# StepperMotorDriver_Ver_0_1.net
KiCad netlist of a schematic drawn in Altium Designer
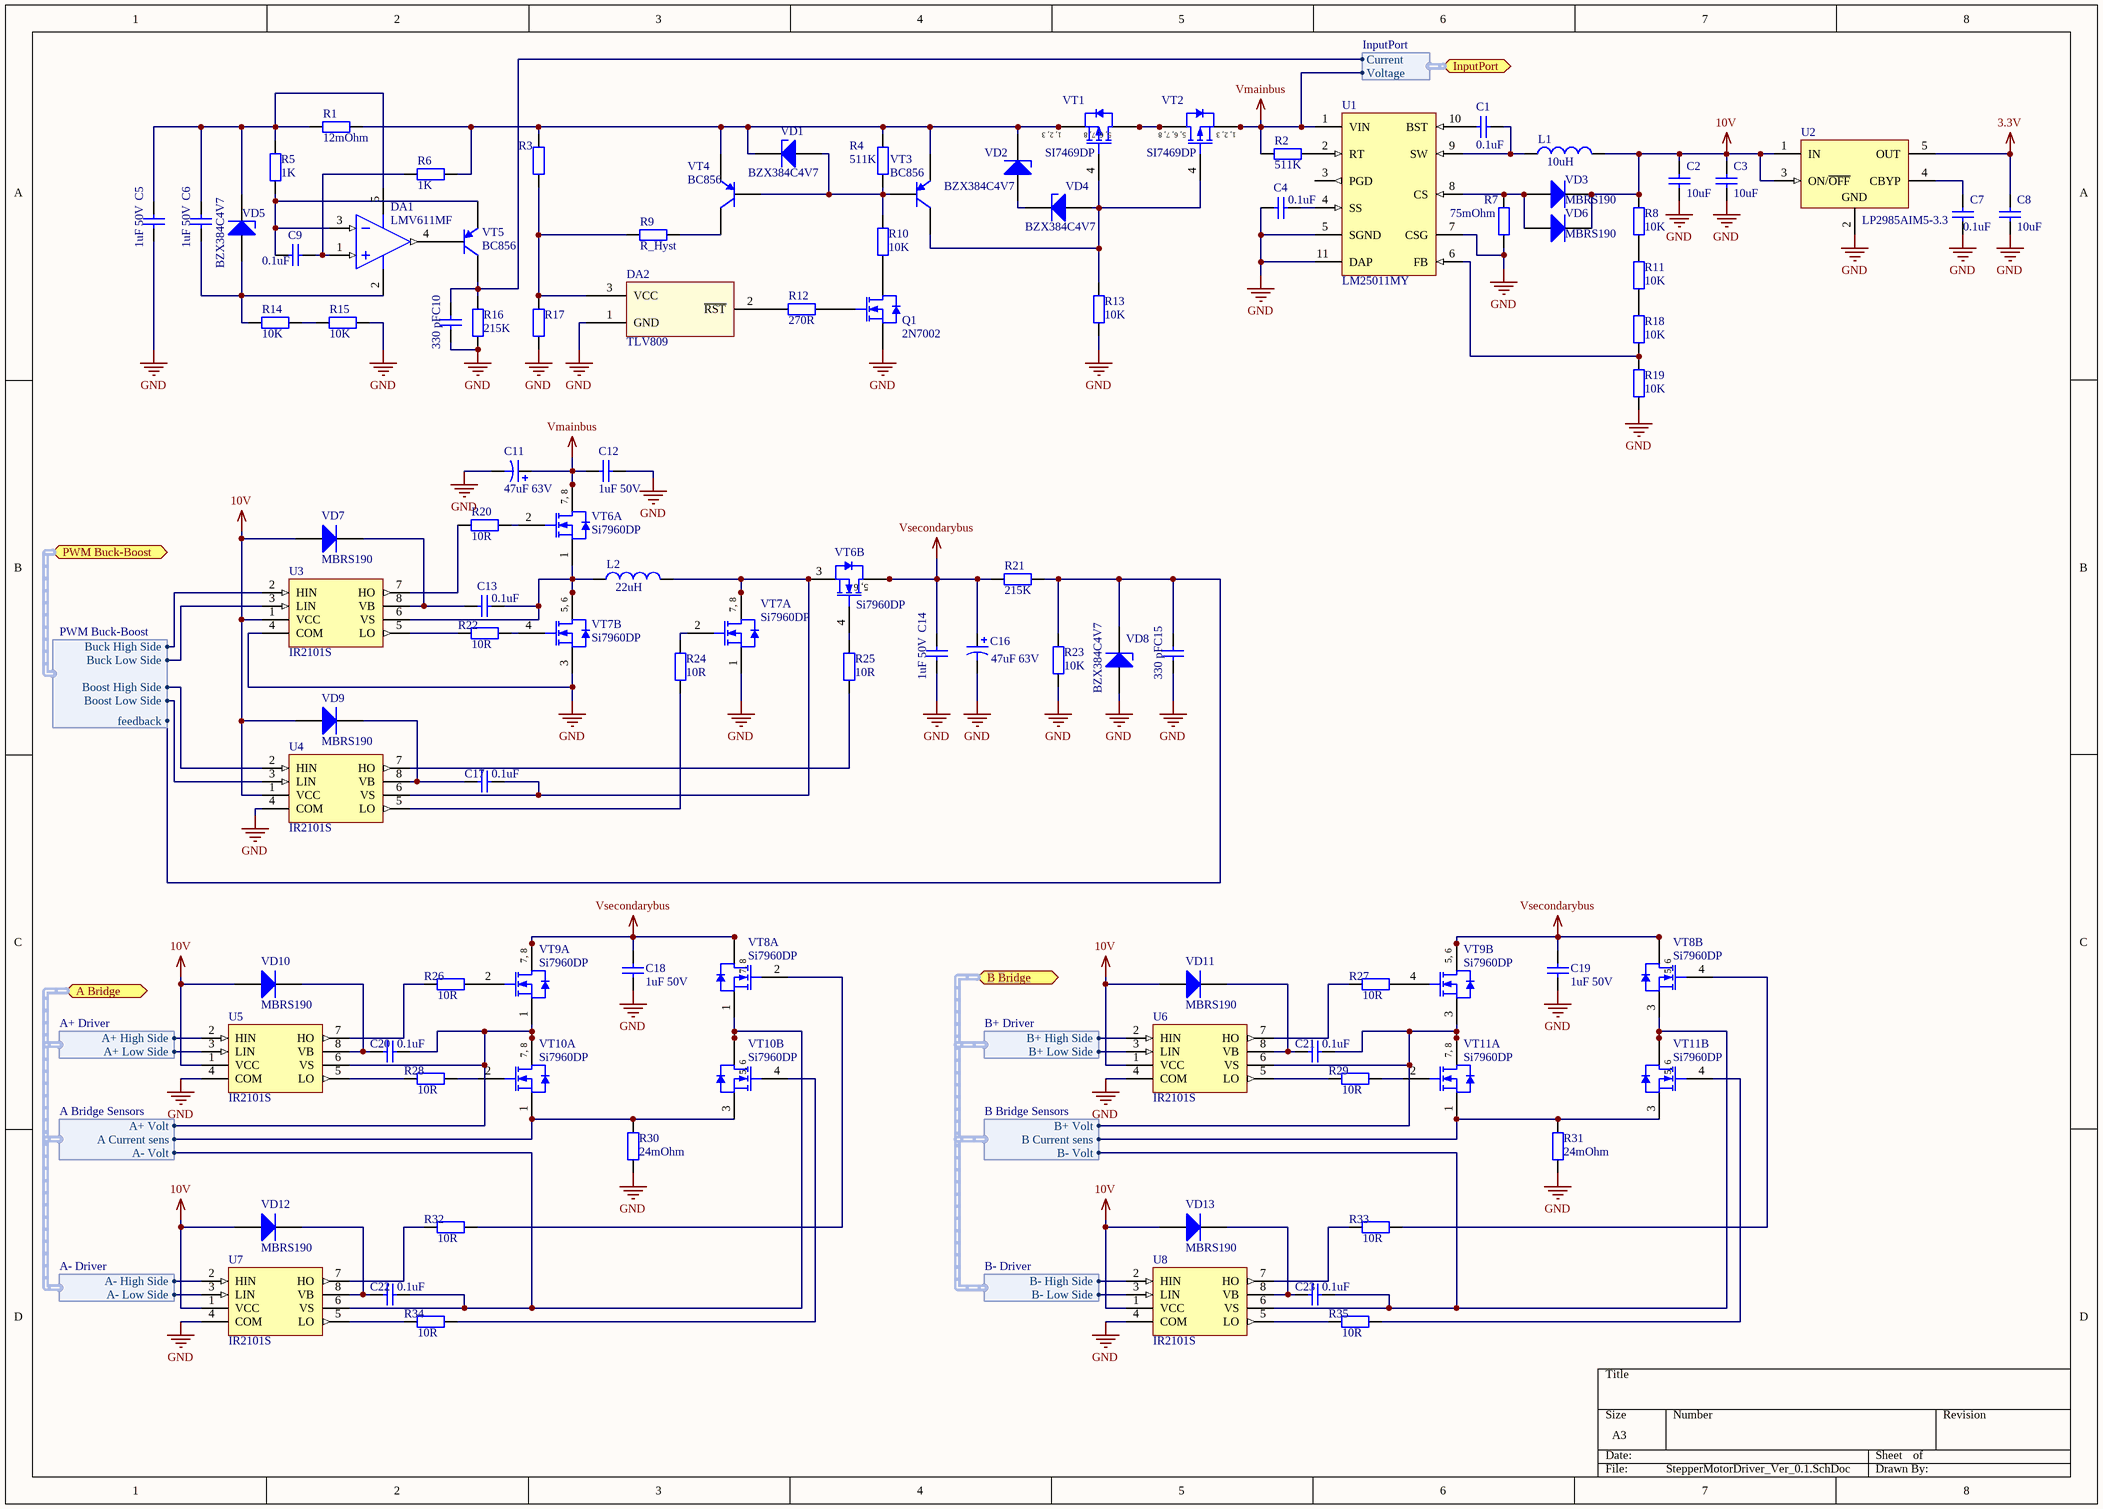
[diagram p0: StepperMotorDriver_Ver_0.1.SchDoc]

(export (version "E")
  (design (tool "Eeschema 10.0.6"))
  (components
    (comp (ref "C1")
      (value "0.1uF")
      (footprint "1608[0603]")
      (description "Capacitor")
      (fields (field (name "PUBLISHER") "Altium Limited"))
      (libsource (lib "SMD") (part "Capacitor"))
    )
    (comp (ref "C2")
      (value "10uF")
      (footprint "C1206")
      (description "Capacitor")
      (fields (field (name "PUBLISHER") "Altium Limited"))
      (libsource (lib "SMD") (part "Capacitor"))
    )
    (comp (ref "C3")
      (value "10uF")
      (footprint "C1206")
      (description "Capacitor")
      (fields (field (name "PUBLISHER") "Altium Limited"))
      (libsource (lib "SMD") (part "Capacitor"))
    )
    (comp (ref "C4")
      (value "0.1uF")
      (footprint "1608[0603]")
      (description "Capacitor")
      (fields (field (name "PUBLISHER") "Altium Limited"))
      (libsource (lib "SMD") (part "Capacitor"))
    )
    (comp (ref "C5")
      (value "1uF 50V")
      (footprint "C0805")
      (description "Capacitor")
      (fields (field (name "PUBLISHER") "Altium Limited"))
      (libsource (lib "SMD") (part "Capacitor"))
    )
    (comp (ref "C6")
      (value "1uF 50V")
      (footprint "C0805")
      (description "Capacitor")
      (fields (field (name "PUBLISHER") "Altium Limited"))
      (libsource (lib "SMD") (part "Capacitor"))
    )
    (comp (ref "C7")
      (value "0.1uF")
      (footprint "1608[0603]")
      (description "Capacitor")
      (fields (field (name "PUBLISHER") "Altium Limited"))
      (libsource (lib "SMD") (part "Capacitor"))
    )
    (comp (ref "C8")
      (value "10uF")
      (footprint "C1206")
      (description "Capacitor")
      (fields (field (name "PUBLISHER") "Altium Limited"))
      (libsource (lib "SMD") (part "Capacitor"))
    )
    (comp (ref "C9")
      (value "0.1uF")
      (footprint "1608[0603]")
      (description "Capacitor")
      (fields (field (name "PUBLISHER") "Altium Limited"))
      (libsource (lib "SMD") (part "Capacitor"))
    )
    (comp (ref "C10")
      (value "330 pF")
      (footprint "1608[0603]")
      (description "Capacitor")
      (fields (field (name "PUBLISHER") "Altium Limited"))
      (libsource (lib "SMD") (part "Capacitor"))
    )
    (comp (ref "C11")
      (value "47uF 63V")
      (footprint "SMD:10x10.5")
      (description "Polarized Capacitor (Radial)")
      (fields (field (name "PUBLISHER") "Altium Limited"))
      (libsource (lib "Miscellaneous Devices") (part "Cap Pol1"))
    )
    (comp (ref "C12")
      (value "1uF 50V")
      (footprint "C0805")
      (description "Capacitor")
      (fields (field (name "PUBLISHER") "Altium Limited"))
      (libsource (lib "SMD") (part "Capacitor"))
    )
    (comp (ref "C13")
      (value "0.1uF")
      (footprint "1608[0603]")
      (description "Capacitor")
      (fields (field (name "PUBLISHER") "Altium Limited"))
      (libsource (lib "SMD") (part "Capacitor"))
    )
    (comp (ref "C14")
      (value "1uF 50V")
      (footprint "C0805")
      (description "Capacitor")
      (fields (field (name "PUBLISHER") "Altium Limited"))
      (libsource (lib "SMD") (part "Capacitor"))
    )
    (comp (ref "C15")
      (value "330 pF")
      (footprint "1608[0603]")
      (description "Capacitor")
      (fields (field (name "PUBLISHER") "Altium Limited"))
      (libsource (lib "SMD") (part "Capacitor"))
    )
    (comp (ref "C16")
      (value "47uF 63V")
      (footprint "10x10.5")
      (description "Polarized Capacitor (Radial)")
      (fields (field (name "PUBLISHER") "Altium Limited"))
      (libsource (lib "Miscellaneous Devices") (part "Cap Pol1"))
    )
    (comp (ref "C17")
      (value "0.1uF")
      (footprint "1608[0603]")
      (description "Capacitor")
      (fields (field (name "PUBLISHER") "Altium Limited"))
      (libsource (lib "SMD") (part "Capacitor"))
    )
    (comp (ref "C18")
      (value "1uF 50V")
      (footprint "C0805")
      (description "Capacitor")
      (fields (field (name "PUBLISHER") "Altium Limited"))
      (libsource (lib "SMD") (part "Capacitor"))
    )
    (comp (ref "C19")
      (value "1uF 50V")
      (footprint "C0805")
      (description "Capacitor")
      (fields (field (name "PUBLISHER") "Altium Limited"))
      (libsource (lib "SMD") (part "Capacitor"))
    )
    (comp (ref "C20")
      (value "0.1uF")
      (footprint "1608[0603]")
      (description "Capacitor")
      (fields (field (name "PUBLISHER") "Altium Limited"))
      (libsource (lib "SMD") (part "Capacitor"))
    )
    (comp (ref "C21")
      (value "0.1uF")
      (footprint "1608[0603]")
      (description "Capacitor")
      (fields (field (name "PUBLISHER") "Altium Limited"))
      (libsource (lib "SMD") (part "Capacitor"))
    )
    (comp (ref "C22")
      (value "0.1uF")
      (footprint "1608[0603]")
      (description "Capacitor")
      (fields (field (name "PUBLISHER") "Altium Limited"))
      (libsource (lib "SMD") (part "Capacitor"))
    )
    (comp (ref "C23")
      (value "0.1uF")
      (footprint "1608[0603]")
      (description "Capacitor")
      (fields (field (name "PUBLISHER") "Altium Limited"))
      (libsource (lib "SMD") (part "Capacitor"))
    )
    (comp (ref "DA1")
      (value "LMV611MF")
      (footprint "MF05A_M")
      (description "Low Power Single Op Amp, 5-pin SOT-23")
      (fields
        (field (name "PARTNUMBER") "LM321MF")
        (field (name "MANUFACTURER") "National Semiconductor")
        (field (name "PUBLISHER") "Altium Limited")
      )
      (libsource (lib "SMD") (part "LMV611MF"))
    )
    (comp (ref "DA2")
      (value "TLV809")
      (footprint "SOT23")
      (description "SuperVisor TI")
      (libsource (lib "SMD") (part "TLV809"))
    )
    (comp (ref "L1")
      (value "10uH")
      (footprint "0402-A")
      (description "Inductor")
      (fields (field (name "PUBLISHER") "Altium Limited"))
      (libsource (lib "SMD") (part "Inductor"))
    )
    (comp (ref "L2")
      (value "22uH")
      (footprint "0402-A")
      (description "Inductor")
      (fields (field (name "PUBLISHER") "Altium Limited"))
      (libsource (lib "SMD") (part "Inductor"))
    )
    (comp (ref "Q1")
      (value "2N7002")
      (footprint "SOT23_N")
      (description "N-channel Enhancement Mode Field-effect Transistor")
      (fields (field (name "PUBLISHER") "Altium Limited"))
      (libsource (lib "Philips Discrete MOSFET - Low Power") (part "2N7002"))
    )
    (comp (ref "R1")
      (value "12mOhm")
      (footprint "Res12mOhm")
      (description "Resistor")
      (fields (field (name "PUBLISHER") "Altium Limited"))
      (libsource (lib "SMD") (part "Resistor"))
    )
    (comp (ref "R2")
      (value "511K")
      (footprint "J1-0603")
      (description "Resistor")
      (fields (field (name "PUBLISHER") "Altium Limited"))
      (libsource (lib "SMD") (part "Resistor"))
    )
    (comp (ref "R3")
      (value "Resistor")
      (footprint "J1-0603")
      (fields (field (name "PUBLISHER") "Altium Limited"))
      (libsource (lib "") (part "Resistor_3"))
    )
    (comp (ref "R4")
      (value "511K")
      (footprint "J1-0603")
      (description "Resistor")
      (fields (field (name "PUBLISHER") "Altium Limited"))
      (libsource (lib "") (part "Resistor_3"))
    )
    (comp (ref "R5")
      (value "1K")
      (footprint "J1-0603")
      (description "Resistor")
      (fields (field (name "PUBLISHER") "Altium Limited"))
      (libsource (lib "") (part "Resistor_1"))
    )
    (comp (ref "R6")
      (value "1K")
      (footprint "J1-0603")
      (description "Resistor")
      (fields (field (name "PUBLISHER") "Altium Limited"))
      (libsource (lib "") (part "Resistor_2"))
    )
    (comp (ref "R7")
      (value "75mOhm")
      (footprint "J1-0603")
      (description "Resistor")
      (fields (field (name "PUBLISHER") "Altium Limited"))
      (libsource (lib "") (part "Resistor_1"))
    )
    (comp (ref "R8")
      (value "10K")
      (footprint "J1-0603")
      (description "Resistor")
      (fields (field (name "PUBLISHER") "Altium Limited"))
      (libsource (lib "") (part "Resistor_1"))
    )
    (comp (ref "R9")
      (value "R_Hyst")
      (footprint "J1-0603")
      (description "Resistor")
      (fields (field (name "PUBLISHER") "Altium Limited"))
      (libsource (lib "SMD") (part "Resistor"))
    )
    (comp (ref "R10")
      (value "10K")
      (footprint "J1-0603")
      (description "Resistor")
      (fields (field (name "PUBLISHER") "Altium Limited"))
      (libsource (lib "") (part "Resistor_3"))
    )
    (comp (ref "R11")
      (value "10K")
      (footprint "J1-0603")
      (description "Resistor")
      (fields (field (name "PUBLISHER") "Altium Limited"))
      (libsource (lib "") (part "Resistor_3"))
    )
    (comp (ref "R12")
      (value "270R")
      (footprint "J1-0603")
      (description "Resistor")
      (fields (field (name "PUBLISHER") "Altium Limited"))
      (libsource (lib "SMD") (part "Resistor"))
    )
    (comp (ref "R13")
      (value "10K")
      (footprint "J1-0603")
      (description "Resistor")
      (fields (field (name "PUBLISHER") "Altium Limited"))
      (libsource (lib "") (part "Resistor_1"))
    )
    (comp (ref "R14")
      (value "10K")
      (footprint "J1-0603")
      (description "Resistor")
      (fields (field (name "PUBLISHER") "Altium Limited"))
      (libsource (lib "SMD") (part "Resistor"))
    )
    (comp (ref "R15")
      (value "10K")
      (footprint "J1-0603")
      (description "Resistor")
      (fields (field (name "PUBLISHER") "Altium Limited"))
      (libsource (lib "SMD") (part "Resistor"))
    )
    (comp (ref "R16")
      (value "215K")
      (footprint "J1-0603")
      (description "Resistor")
      (fields (field (name "PUBLISHER") "Altium Limited"))
      (libsource (lib "") (part "Resistor_1"))
    )
    (comp (ref "R17")
      (value "Resistor")
      (footprint "J1-0603")
      (fields (field (name "PUBLISHER") "Altium Limited"))
      (libsource (lib "") (part "Resistor_3"))
    )
    (comp (ref "R18")
      (value "10K")
      (footprint "J1-0603")
      (description "Resistor")
      (fields (field (name "PUBLISHER") "Altium Limited"))
      (libsource (lib "") (part "Resistor_1"))
    )
    (comp (ref "R19")
      (value "10K")
      (footprint "J1-0603")
      (description "Resistor")
      (fields (field (name "PUBLISHER") "Altium Limited"))
      (libsource (lib "") (part "Resistor_1"))
    )
    (comp (ref "R20")
      (value "10R")
      (footprint "J1-0603")
      (description "Resistor")
      (fields (field (name "PUBLISHER") "Altium Limited"))
      (libsource (lib "SMD") (part "Resistor"))
    )
    (comp (ref "R21")
      (value "215K")
      (footprint "J1-0603")
      (description "Resistor")
      (fields (field (name "PUBLISHER") "Altium Limited"))
      (libsource (lib "") (part "Resistor_2"))
    )
    (comp (ref "R22")
      (value "10R")
      (footprint "J1-0603")
      (description "Resistor")
      (fields (field (name "PUBLISHER") "Altium Limited"))
      (libsource (lib "SMD") (part "Resistor"))
    )
    (comp (ref "R23")
      (value "10K")
      (footprint "J1-0603")
      (description "Resistor")
      (fields (field (name "PUBLISHER") "Altium Limited"))
      (libsource (lib "") (part "Resistor_1"))
    )
    (comp (ref "R24")
      (value "10R")
      (footprint "J1-0603")
      (description "Resistor")
      (fields (field (name "PUBLISHER") "Altium Limited"))
      (libsource (lib "") (part "Resistor_1"))
    )
    (comp (ref "R25")
      (value "10R")
      (footprint "J1-0603")
      (description "Resistor")
      (fields (field (name "PUBLISHER") "Altium Limited"))
      (libsource (lib "") (part "Resistor_1"))
    )
    (comp (ref "R26")
      (value "10R")
      (footprint "J1-0603")
      (description "Resistor")
      (fields (field (name "PUBLISHER") "Altium Limited"))
      (libsource (lib "SMD") (part "Resistor"))
    )
    (comp (ref "R27")
      (value "10R")
      (footprint "J1-0603")
      (description "Resistor")
      (fields (field (name "PUBLISHER") "Altium Limited"))
      (libsource (lib "SMD") (part "Resistor"))
    )
    (comp (ref "R28")
      (value "10R")
      (footprint "J1-0603")
      (description "Resistor")
      (fields (field (name "PUBLISHER") "Altium Limited"))
      (libsource (lib "SMD") (part "Resistor"))
    )
    (comp (ref "R29")
      (value "10R")
      (footprint "J1-0603")
      (description "Resistor")
      (fields (field (name "PUBLISHER") "Altium Limited"))
      (libsource (lib "SMD") (part "Resistor"))
    )
    (comp (ref "R30")
      (value "24mOhm")
      (footprint "Res24mOhm")
      (description "Resistor")
      (fields (field (name "PUBLISHER") "Altium Limited"))
      (libsource (lib "") (part "Resistor_1"))
    )
    (comp (ref "R31")
      (value "24mOhm")
      (footprint "Res24mOhm")
      (description "Resistor")
      (fields (field (name "PUBLISHER") "Altium Limited"))
      (libsource (lib "") (part "Resistor_1"))
    )
    (comp (ref "R32")
      (value "10R")
      (footprint "J1-0603")
      (description "Resistor")
      (fields (field (name "PUBLISHER") "Altium Limited"))
      (libsource (lib "SMD") (part "Resistor"))
    )
    (comp (ref "R33")
      (value "10R")
      (footprint "J1-0603")
      (description "Resistor")
      (fields (field (name "PUBLISHER") "Altium Limited"))
      (libsource (lib "SMD") (part "Resistor"))
    )
    (comp (ref "R34")
      (value "10R")
      (footprint "J1-0603")
      (description "Resistor")
      (fields (field (name "PUBLISHER") "Altium Limited"))
      (libsource (lib "SMD") (part "Resistor"))
    )
    (comp (ref "R35")
      (value "10R")
      (footprint "J1-0603")
      (description "Resistor")
      (fields (field (name "PUBLISHER") "Altium Limited"))
      (libsource (lib "SMD") (part "Resistor"))
    )
    (comp (ref "U1")
      (value "LM25011MY")
      (footprint "MUC10A_N")
      (description "42V, 2A Constant On-Time Switching Regulator with Adjustable Current Limit, 10-pin eMSOP")
      (fields
        (field (name "MANUFACTURER") "National Semiconductor")
        (field (name "PUBLISHER") "Altium Limited")
      )
      (libsource (lib "NSC Switcher") (part "LM25011MY"))
    )
    (comp (ref "U2")
      (value "LP2985AIM5-3.3")
      (footprint "MF05A_N")
      (description "Micropower 150 mA Low-Noise Ultra Low-Dropout Regulator, 5-pin SOT-23")
      (fields
        (field (name "MANUFACTURER") "National Semiconductor")
        (field (name "PUBLISHER") "Altium Limited")
      )
      (libsource (lib "NSC LDO") (part "LP2985AIM5-3.3"))
    )
    (comp (ref "U3")
      (value "IR2101S")
      (footprint "SO-8_N")
      (description "High and Low Side Driver")
      (fields (field (name "PUBLISHER") "Altium Limited"))
      (libsource (lib "IR Interface Bridge Driver") (part "IR2101S"))
    )
    (comp (ref "U4")
      (value "IR2101S")
      (footprint "SO-8_N")
      (description "High and Low Side Driver")
      (fields (field (name "PUBLISHER") "Altium Limited"))
      (libsource (lib "IR Interface Bridge Driver") (part "IR2101S"))
    )
    (comp (ref "U5")
      (value "IR2101S")
      (footprint "SO-8_N")
      (description "High and Low Side Driver")
      (fields (field (name "PUBLISHER") "Altium Limited"))
      (libsource (lib "IR Interface Bridge Driver") (part "IR2101S"))
    )
    (comp (ref "U6")
      (value "IR2101S")
      (footprint "SO-8_N")
      (description "High and Low Side Driver")
      (fields (field (name "PUBLISHER") "Altium Limited"))
      (libsource (lib "IR Interface Bridge Driver") (part "IR2101S"))
    )
    (comp (ref "U7")
      (value "IR2101S")
      (footprint "SO-8_N")
      (description "High and Low Side Driver")
      (fields (field (name "PUBLISHER") "Altium Limited"))
      (libsource (lib "IR Interface Bridge Driver") (part "IR2101S"))
    )
    (comp (ref "U8")
      (value "IR2101S")
      (footprint "SO-8_N")
      (description "High and Low Side Driver")
      (fields (field (name "PUBLISHER") "Altium Limited"))
      (libsource (lib "IR Interface Bridge Driver") (part "IR2101S"))
    )
    (comp (ref "VD1")
      (value "BZX384C4V7")
      (footprint "SMD:SOD323")
      (description "Zenner Diode")
      (fields (field (name "PUBLISHER") "Altium Limited"))
      (libsource (lib "SMD") (part "BZX384C5V6"))
    )
    (comp (ref "VD2")
      (value "BZX384C4V7")
      (footprint "SOD323")
      (description "Zenner Diode")
      (fields (field (name "PUBLISHER") "Altium Limited"))
      (libsource (lib "SMD") (part "BZX384C5V6"))
    )
    (comp (ref "VD3")
      (value "MBRS190")
      (footprint "DIOM4336X24N")
      (description "Silicon Zener Diode")
      (fields (field (name "PUBLISHER") "Altium Limited"))
      (libsource (lib "SMD") (part "MBRS190"))
    )
    (comp (ref "VD4")
      (value "BZX384C4V7")
      (footprint "SOD323")
      (description "Zenner Diode")
      (fields (field (name "PUBLISHER") "Altium Limited"))
      (libsource (lib "SMD") (part "BZX384C5V6"))
    )
    (comp (ref "VD5")
      (value "BZX384C4V7")
      (footprint "SOD323")
      (description "Zenner Diode")
      (fields (field (name "PUBLISHER") "Altium Limited"))
      (libsource (lib "SMD") (part "BZX384C5V6"))
    )
    (comp (ref "VD6")
      (value "MBRS190")
      (footprint "DIOM4336X24N")
      (description "Silicon Zener Diode")
      (fields (field (name "PUBLISHER") "Altium Limited"))
      (libsource (lib "SMD") (part "MBRS190"))
    )
    (comp (ref "VD7")
      (value "MBRS190")
      (footprint "DIOM4336X24N")
      (description "Silicon Zener Diode")
      (fields (field (name "PUBLISHER") "Altium Limited"))
      (libsource (lib "SMD") (part "MBRS190"))
    )
    (comp (ref "VD8")
      (value "BZX384C4V7")
      (footprint "SOD323")
      (description "Zenner Diode")
      (fields (field (name "PUBLISHER") "Altium Limited"))
      (libsource (lib "SMD") (part "BZX384C5V6"))
    )
    (comp (ref "VD9")
      (value "MBRS190")
      (footprint "DIOM4336X24N")
      (description "Silicon Zener Diode")
      (fields (field (name "PUBLISHER") "Altium Limited"))
      (libsource (lib "SMD") (part "MBRS190"))
    )
    (comp (ref "VD10")
      (value "MBRS190")
      (footprint "DIOM4336X24N")
      (description "Silicon Zener Diode")
      (fields (field (name "PUBLISHER") "Altium Limited"))
      (libsource (lib "SMD") (part "MBRS190"))
    )
    (comp (ref "VD11")
      (value "MBRS190")
      (footprint "DIOM4336X24N")
      (description "Silicon Zener Diode")
      (fields (field (name "PUBLISHER") "Altium Limited"))
      (libsource (lib "SMD") (part "MBRS190"))
    )
    (comp (ref "VD12")
      (value "MBRS190")
      (footprint "DIOM4336X24N")
      (description "Silicon Zener Diode")
      (fields (field (name "PUBLISHER") "Altium Limited"))
      (libsource (lib "SMD") (part "MBRS190"))
    )
    (comp (ref "VD13")
      (value "MBRS190")
      (footprint "DIOM4336X24N")
      (description "Silicon Zener Diode")
      (fields (field (name "PUBLISHER") "Altium Limited"))
      (libsource (lib "SMD") (part "MBRS190"))
    )
    (comp (ref "VT1")
      (value "SI7469DP")
      (footprint "PowerPak_SO-8")
      (description "P-Channel 80V (D-S)  MOSFET")
      (fields (field (name "PUBLISHER") "Altium Limited"))
      (libsource (lib "SMD") (part "SI7469DP"))
    )
    (comp (ref "VT2")
      (value "SI7469DP")
      (footprint "PowerPak_SO-8")
      (description "P-Channel 80V (D-S)  MOSFET")
      (fields (field (name "PUBLISHER") "Altium Limited"))
      (libsource (lib "SMD") (part "SI7469DP"))
    )
    (comp (ref "VT3")
      (value "BC856")
      (footprint "SOT23_N")
      (description "PNP General-purpose Transistor")
      (fields (field (name "PUBLISHER") "Altium Limited"))
      (libsource (lib "Philips Discrete BJT - Low Power") (part "BC856"))
    )
    (comp (ref "VT4")
      (value "BC856")
      (footprint "SOT23_N")
      (description "PNP General-purpose Transistor")
      (fields (field (name "PUBLISHER") "Altium Limited"))
      (libsource (lib "Philips Discrete BJT - Low Power") (part "BC856"))
    )
    (comp (ref "VT5")
      (value "BC856")
      (footprint "SOT23_N")
      (description "PNP General-purpose Transistor")
      (fields (field (name "PUBLISHER") "Altium Limited"))
      (libsource (lib "Philips Discrete BJT - Low Power") (part "BC856"))
    )
    (comp (ref "VT6")
      (value "Si7960DP")
      (footprint "PowerPak_SO-8")
      (description "Dual N-Channel 60V (D-S), 175'C  MOSFET")
      (fields (field (name "PUBLISHER") "Altium Limited"))
      (libsource (lib "SMD") (part "Si7960DP"))
    )
    (comp (ref "VT7")
      (value "Si7960DP")
      (footprint "PowerPak_SO-8")
      (description "Dual N-Channel 60V (D-S), 175'C  MOSFET")
      (fields (field (name "PUBLISHER") "Altium Limited"))
      (libsource (lib "SMD") (part "Si7960DP"))
    )
    (comp (ref "VT8")
      (value "Si7960DP")
      (footprint "PowerPak_SO-8")
      (description "Dual N-Channel 60V (D-S), 175'C  MOSFET")
      (fields (field (name "PUBLISHER") "Altium Limited"))
      (libsource (lib "SMD") (part "Si7960DP"))
    )
    (comp (ref "VT9")
      (value "Si7960DP")
      (footprint "PowerPak_SO-8")
      (description "Dual N-Channel 60V (D-S), 175'C  MOSFET")
      (fields (field (name "PUBLISHER") "Altium Limited"))
      (libsource (lib "SMD") (part "Si7960DP"))
    )
    (comp (ref "VT10")
      (value "Si7960DP")
      (footprint "PowerPak_SO-8")
      (description "Dual N-Channel 60V (D-S), 175'C  MOSFET")
      (fields (field (name "PUBLISHER") "Altium Limited"))
      (libsource (lib "SMD") (part "Si7960DP"))
    )
    (comp (ref "VT11")
      (value "Si7960DP")
      (footprint "PowerPak_SO-8")
      (description "Dual N-Channel 60V (D-S), 175'C  MOSFET")
      (fields (field (name "PUBLISHER") "Altium Limited"))
      (libsource (lib "SMD") (part "Si7960DP"))
    )
  )
  (nets
    (net (code "13") (name "/A Current sens") (class "Default")
      (node (ref "R30") (pin "2") (pinfunction "2_2") (pintype "passive"))
      (node (ref "VT10") (pin "1") (pinfunction "S_1") (pintype "passive"))
      (node (ref "VT10") (pin "3") (pinfunction "S_3") (pintype "passive"))
    )
    (net (code "14") (name "/A+ High Side") (class "Default")
      (node (ref "U5") (pin "2") (pinfunction "HIN_2") (pintype "input"))
    )
    (net (code "15") (name "/A+ Low Side") (class "Default")
      (node (ref "U5") (pin "3") (pinfunction "LIN_3") (pintype "input"))
    )
    (net (code "16") (name "/A+ Volt") (class "Default")
      (node (ref "C20") (pin "2") (pinfunction "2_2") (pintype "passive"))
      (node (ref "U5") (pin "6") (pinfunction "VS_6") (pintype "power_in"))
      (node (ref "VT10") (pin "7") (pinfunction "D_7") (pintype "passive"))
      (node (ref "VT10") (pin "8") (pinfunction "D_8") (pintype "passive"))
      (node (ref "VT9") (pin "1") (pinfunction "S_1") (pintype "passive"))
    )
    (net (code "17") (name "/A- High Side") (class "Default")
      (node (ref "U7") (pin "2") (pinfunction "HIN_2") (pintype "input"))
    )
    (net (code "18") (name "/A- Low Side") (class "Default")
      (node (ref "U7") (pin "3") (pinfunction "LIN_3") (pintype "input"))
    )
    (net (code "19") (name "/A- Volt") (class "Default")
      (node (ref "C22") (pin "2") (pinfunction "2_2") (pintype "passive"))
      (node (ref "U7") (pin "6") (pinfunction "VS_6") (pintype "power_in"))
      (node (ref "VT10") (pin "5") (pinfunction "D_5") (pintype "passive"))
      (node (ref "VT10") (pin "6") (pinfunction "D_6") (pintype "passive"))
      (node (ref "VT8") (pin "1") (pinfunction "S_1") (pintype "passive"))
    )
    (net (code "20") (name "/B Current sens") (class "Default")
      (node (ref "R31") (pin "2") (pinfunction "2_2") (pintype "passive"))
      (node (ref "VT11") (pin "1") (pinfunction "S_1") (pintype "passive"))
      (node (ref "VT11") (pin "3") (pinfunction "S_3") (pintype "passive"))
    )
    (net (code "21") (name "/B+ High Side") (class "Default")
      (node (ref "U6") (pin "2") (pinfunction "HIN_2") (pintype "input"))
    )
    (net (code "22") (name "/B+ Low Side") (class "Default")
      (node (ref "U6") (pin "3") (pinfunction "LIN_3") (pintype "input"))
    )
    (net (code "23") (name "/B+ Volt") (class "Default")
      (node (ref "C21") (pin "2") (pinfunction "2_2") (pintype "passive"))
      (node (ref "U6") (pin "6") (pinfunction "VS_6") (pintype "power_in"))
      (node (ref "VT11") (pin "7") (pinfunction "D_7") (pintype "passive"))
      (node (ref "VT11") (pin "8") (pinfunction "D_8") (pintype "passive"))
      (node (ref "VT9") (pin "3") (pinfunction "S_3") (pintype "passive"))
    )
    (net (code "24") (name "/B- High Side") (class "Default")
      (node (ref "U8") (pin "2") (pinfunction "HIN_2") (pintype "input"))
    )
    (net (code "25") (name "/B- Low Side") (class "Default")
      (node (ref "U8") (pin "3") (pinfunction "LIN_3") (pintype "input"))
    )
    (net (code "26") (name "/B- Volt") (class "Default")
      (node (ref "C23") (pin "2") (pinfunction "2_2") (pintype "passive"))
      (node (ref "U8") (pin "6") (pinfunction "VS_6") (pintype "power_in"))
      (node (ref "VT11") (pin "5") (pinfunction "D_5") (pintype "passive"))
      (node (ref "VT11") (pin "6") (pinfunction "D_6") (pintype "passive"))
      (node (ref "VT8") (pin "3") (pinfunction "S_3") (pintype "passive"))
    )
    (net (code "27") (name "/Boost High Side") (class "Default")
      (node (ref "U4") (pin "2") (pinfunction "HIN_2") (pintype "input"))
    )
    (net (code "28") (name "/Boost Low Side") (class "Default")
      (node (ref "U4") (pin "3") (pinfunction "LIN_3") (pintype "input"))
    )
    (net (code "29") (name "/Buck High Side") (class "Default")
      (node (ref "U3") (pin "2") (pinfunction "HIN_2") (pintype "input"))
    )
    (net (code "30") (name "/Buck Low Side") (class "Default")
      (node (ref "U3") (pin "3") (pinfunction "LIN_3") (pintype "input"))
    )
    (net (code "31") (name "/Current") (class "Default")
      (node (ref "C10") (pin "2") (pinfunction "2_2") (pintype "passive"))
      (node (ref "R16") (pin "2") (pinfunction "2_2") (pintype "passive"))
      (node (ref "VT5") (pin "3") (pinfunction "C_3") (pintype "passive"))
    )
    (net (code "32") (name "/feedback") (class "Default")
      (node (ref "C15") (pin "2") (pinfunction "2_2") (pintype "passive"))
      (node (ref "R21") (pin "1") (pinfunction "1_1") (pintype "passive"))
      (node (ref "R23") (pin "2") (pinfunction "2_2") (pintype "passive"))
      (node (ref "VD8") (pin "1") (pinfunction "K_1") (pintype "passive"))
    )
    (net (code "41") (name "3.3V") (class "Default")
      (node (ref "C8") (pin "2") (pinfunction "2_2") (pintype "passive"))
      (node (ref "U2") (pin "5") (pinfunction "OUT_5") (pintype "power_in"))
    )
    (net (code "42") (name "10V") (class "Default")
      (node (ref "C2") (pin "2") (pinfunction "2_2") (pintype "passive"))
      (node (ref "C3") (pin "2") (pinfunction "2_2") (pintype "passive"))
      (node (ref "L1") (pin "2") (pinfunction "2_2") (pintype "passive"))
      (node (ref "R8") (pin "2") (pinfunction "2_2") (pintype "passive"))
      (node (ref "U2") (pin "1") (pinfunction "IN_1") (pintype "power_in"))
      (node (ref "U2") (pin "3") (pinfunction "ON/~{OFF}_3") (pintype "input"))
      (node (ref "U3") (pin "1") (pinfunction "VCC_1") (pintype "power_in"))
      (node (ref "U4") (pin "1") (pinfunction "VCC_1") (pintype "power_in"))
      (node (ref "U5") (pin "1") (pinfunction "VCC_1") (pintype "power_in"))
      (node (ref "U6") (pin "1") (pinfunction "VCC_1") (pintype "power_in"))
      (node (ref "U7") (pin "1") (pinfunction "VCC_1") (pintype "power_in"))
      (node (ref "U8") (pin "1") (pinfunction "VCC_1") (pintype "power_in"))
      (node (ref "VD10") (pin "1") (pinfunction "A_1") (pintype "passive"))
      (node (ref "VD11") (pin "1") (pinfunction "A_1") (pintype "passive"))
      (node (ref "VD12") (pin "1") (pinfunction "A_1") (pintype "passive"))
      (node (ref "VD13") (pin "1") (pinfunction "A_1") (pintype "passive"))
      (node (ref "VD3") (pin "2") (pinfunction "K_2") (pintype "passive"))
      (node (ref "VD6") (pin "2") (pinfunction "K_2") (pintype "passive"))
      (node (ref "VD7") (pin "1") (pinfunction "A_1") (pintype "passive"))
      (node (ref "VD9") (pin "1") (pinfunction "A_1") (pintype "passive"))
    )
    (net (code "43") (name "GND") (class "Default")
      (node (ref "C10") (pin "1") (pinfunction "1_1") (pintype "passive"))
      (node (ref "C11") (pin "2") (pinfunction "2_2") (pintype "passive"))
      (node (ref "C12") (pin "1") (pinfunction "1_1") (pintype "passive"))
      (node (ref "C14") (pin "1") (pinfunction "1_1") (pintype "passive"))
      (node (ref "C15") (pin "1") (pinfunction "1_1") (pintype "passive"))
      (node (ref "C16") (pin "2") (pinfunction "2_2") (pintype "passive"))
      (node (ref "C18") (pin "2") (pinfunction "2_2") (pintype "passive"))
      (node (ref "C19") (pin "2") (pinfunction "2_2") (pintype "passive"))
      (node (ref "C2") (pin "1") (pinfunction "1_1") (pintype "passive"))
      (node (ref "C3") (pin "1") (pinfunction "1_1") (pintype "passive"))
      (node (ref "C4") (pin "1") (pinfunction "1_1") (pintype "passive"))
      (node (ref "C5") (pin "1") (pinfunction "1_1") (pintype "passive"))
      (node (ref "C7") (pin "1") (pinfunction "1_1") (pintype "passive"))
      (node (ref "C8") (pin "1") (pinfunction "1_1") (pintype "passive"))
      (node (ref "DA2") (pin "1") (pinfunction "GND_1") (pintype "passive"))
      (node (ref "Q1") (pin "2") (pinfunction "S_2") (pintype "passive"))
      (node (ref "R13") (pin "1") (pinfunction "1_1") (pintype "passive"))
      (node (ref "R15") (pin "2") (pinfunction "2_2") (pintype "passive"))
      (node (ref "R16") (pin "1") (pinfunction "1_1") (pintype "passive"))
      (node (ref "R17") (pin "2") (pinfunction "2_2") (pintype "passive"))
      (node (ref "R19") (pin "1") (pinfunction "1_1") (pintype "passive"))
      (node (ref "R23") (pin "1") (pinfunction "1_1") (pintype "passive"))
      (node (ref "R30") (pin "1") (pinfunction "1_1") (pintype "passive"))
      (node (ref "R31") (pin "1") (pinfunction "1_1") (pintype "passive"))
      (node (ref "R7") (pin "1") (pinfunction "1_1") (pintype "passive"))
      (node (ref "U1") (pin "11") (pinfunction "DAP_11") (pintype "power_in"))
      (node (ref "U1") (pin "5") (pinfunction "SGND_5") (pintype "power_in"))
      (node (ref "U1") (pin "7") (pinfunction "CSG_7") (pintype "power_in"))
      (node (ref "U2") (pin "2") (pinfunction "GND_2") (pintype "power_in"))
      (node (ref "U3") (pin "4") (pinfunction "COM_4") (pintype "power_in"))
      (node (ref "U4") (pin "4") (pinfunction "COM_4") (pintype "power_in"))
      (node (ref "U5") (pin "4") (pinfunction "COM_4") (pintype "power_in"))
      (node (ref "U6") (pin "4") (pinfunction "COM_4") (pintype "power_in"))
      (node (ref "U7") (pin "4") (pinfunction "COM_4") (pintype "power_in"))
      (node (ref "U8") (pin "4") (pinfunction "COM_4") (pintype "power_in"))
      (node (ref "VD8") (pin "2") (pinfunction "A_2") (pintype "passive"))
      (node (ref "VT7") (pin "1") (pinfunction "S_1") (pintype "passive"))
      (node (ref "VT7") (pin "3") (pinfunction "S_3") (pintype "passive"))
    )
    (net (code "44") (name "Net-(DA1-IN+)") (class "Default")
      (node (ref "C9") (pin "2") (pinfunction "2_2") (pintype "passive"))
      (node (ref "DA1") (pin "1") (pinfunction "IN+_1") (pintype "input"))
      (node (ref "R6") (pin "2") (pinfunction "2_2") (pintype "passive"))
    )
    (net (code "45") (name "Net-(DA1-IN-)") (class "Default")
      (node (ref "C9") (pin "1") (pinfunction "1_1") (pintype "passive"))
      (node (ref "DA1") (pin "3") (pinfunction "IN-_3") (pintype "input"))
      (node (ref "R5") (pin "1") (pinfunction "1_1") (pintype "passive"))
      (node (ref "VT5") (pin "2") (pinfunction "E_2") (pintype "passive"))
    )
    (net (code "46") (name "Net-(DA1-OUT)") (class "Default")
      (node (ref "DA1") (pin "4") (pinfunction "OUT_4") (pintype "output"))
      (node (ref "VT5") (pin "1") (pinfunction "B_1") (pintype "passive"))
    )
    (net (code "47") (name "Net-(DA1-V+)") (class "Default")
      (node (ref "C5") (pin "2") (pinfunction "2_2") (pintype "passive"))
      (node (ref "C6") (pin "2") (pinfunction "2_2") (pintype "passive"))
      (node (ref "DA1") (pin "5") (pinfunction "V+_5") (pintype "power_in"))
      (node (ref "R1") (pin "1") (pinfunction "1_1") (pintype "passive"))
      (node (ref "R5") (pin "2") (pinfunction "2_2") (pintype "passive"))
      (node (ref "VD5") (pin "1") (pinfunction "K_1") (pintype "passive"))
    )
    (net (code "48") (name "Net-(DA1-V-)") (class "Default")
      (node (ref "C6") (pin "1") (pinfunction "1_1") (pintype "passive"))
      (node (ref "DA1") (pin "2") (pinfunction "V-_2") (pintype "power_in"))
      (node (ref "R14") (pin "1") (pinfunction "1_1") (pintype "passive"))
      (node (ref "VD5") (pin "2") (pinfunction "A_2") (pintype "passive"))
    )
    (net (code "49") (name "Net-(DA2-VCC)") (class "Default")
      (node (ref "DA2") (pin "3") (pinfunction "VCC_3") (pintype "passive"))
      (node (ref "R17") (pin "1") (pinfunction "1_1") (pintype "passive"))
      (node (ref "R3") (pin "2") (pinfunction "2_2") (pintype "passive"))
      (node (ref "R9") (pin "1") (pinfunction "1_1") (pintype "passive"))
    )
    (net (code "50") (name "Net-(DA2-~{RST})") (class "Default")
      (node (ref "DA2") (pin "2") (pinfunction "~{RST}_2") (pintype "passive"))
      (node (ref "R12") (pin "1") (pinfunction "1_1") (pintype "passive"))
    )
    (net (code "51") (name "Net-(Q1-D)") (class "Default")
      (node (ref "Q1") (pin "3") (pinfunction "D_3") (pintype "passive"))
      (node (ref "R10") (pin "2") (pinfunction "2_2") (pintype "passive"))
    )
    (net (code "52") (name "Net-(Q1-G)") (class "Default")
      (node (ref "Q1") (pin "1") (pinfunction "G_1") (pintype "passive"))
      (node (ref "R12") (pin "2") (pinfunction "2_2") (pintype "passive"))
    )
    (net (code "53") (name "Net-(R11-Pad1)") (class "Default")
      (node (ref "R11") (pin "1") (pinfunction "1_1") (pintype "passive"))
      (node (ref "R8") (pin "1") (pinfunction "1_1") (pintype "passive"))
    )
    (net (code "54") (name "Net-(R11-Pad2)") (class "Default")
      (node (ref "R11") (pin "2") (pinfunction "2_2") (pintype "passive"))
      (node (ref "R18") (pin "2") (pinfunction "2_2") (pintype "passive"))
    )
    (net (code "55") (name "Net-(R14-Pad2)") (class "Default")
      (node (ref "R14") (pin "2") (pinfunction "2_2") (pintype "passive"))
      (node (ref "R15") (pin "1") (pinfunction "1_1") (pintype "passive"))
    )
    (net (code "56") (name "Net-(U1-BST)") (class "Default")
      (node (ref "C1") (pin "2") (pinfunction "2_2") (pintype "passive"))
      (node (ref "U1") (pin "10") (pinfunction "BST_10") (pintype "input"))
    )
    (net (code "57") (name "Net-(U1-CS)") (class "Default")
      (node (ref "R7") (pin "2") (pinfunction "2_2") (pintype "passive"))
      (node (ref "U1") (pin "8") (pinfunction "CS_8") (pintype "input"))
      (node (ref "VD3") (pin "1") (pinfunction "A_1") (pintype "passive"))
      (node (ref "VD6") (pin "1") (pinfunction "A_1") (pintype "passive"))
    )
    (net (code "58") (name "Net-(U1-FB)") (class "Default")
      (node (ref "R18") (pin "1") (pinfunction "1_1") (pintype "passive"))
      (node (ref "R19") (pin "2") (pinfunction "2_2") (pintype "passive"))
      (node (ref "U1") (pin "6") (pinfunction "FB_6") (pintype "input"))
    )
    (net (code "59") (name "Net-(U1-RT)") (class "Default")
      (node (ref "R2") (pin "2") (pinfunction "2_2") (pintype "passive"))
      (node (ref "U1") (pin "2") (pinfunction "RT_2") (pintype "input"))
    )
    (net (code "60") (name "Net-(U1-SS)") (class "Default")
      (node (ref "C4") (pin "2") (pinfunction "2_2") (pintype "passive"))
      (node (ref "U1") (pin "4") (pinfunction "SS_4") (pintype "input"))
    )
    (net (code "61") (name "Net-(U1-SW)") (class "Default")
      (node (ref "C1") (pin "1") (pinfunction "1_1") (pintype "passive"))
      (node (ref "L1") (pin "1") (pinfunction "1_1") (pintype "passive"))
      (node (ref "U1") (pin "9") (pinfunction "SW_9") (pintype "input"))
    )
    (net (code "62") (name "Net-(U2-CBYP)") (class "Default")
      (node (ref "C7") (pin "2") (pinfunction "2_2") (pintype "passive"))
      (node (ref "U2") (pin "4") (pinfunction "CBYP_4") (pintype "passive"))
    )
    (net (code "63") (name "Net-(U3-HO)") (class "Default")
      (node (ref "R20") (pin "1") (pinfunction "1_1") (pintype "passive"))
      (node (ref "U3") (pin "7") (pinfunction "HO_7") (pintype "output"))
    )
    (net (code "64") (name "Net-(U3-LO)") (class "Default")
      (node (ref "R22") (pin "1") (pinfunction "1_1") (pintype "passive"))
      (node (ref "U3") (pin "5") (pinfunction "LO_5") (pintype "output"))
    )
    (net (code "65") (name "Net-(U3-VB)") (class "Default")
      (node (ref "C13") (pin "1") (pinfunction "1_1") (pintype "passive"))
      (node (ref "U3") (pin "8") (pinfunction "VB_8") (pintype "power_in"))
      (node (ref "VD7") (pin "2") (pinfunction "K_2") (pintype "passive"))
    )
    (net (code "66") (name "Net-(U3-VS)") (class "Default")
      (node (ref "C13") (pin "2") (pinfunction "2_2") (pintype "passive"))
      (node (ref "L2") (pin "1") (pinfunction "1_1") (pintype "passive"))
      (node (ref "U3") (pin "6") (pinfunction "VS_6") (pintype "power_in"))
      (node (ref "VT6") (pin "1") (pinfunction "S_1") (pintype "passive"))
      (node (ref "VT7") (pin "5") (pinfunction "D_5") (pintype "passive"))
      (node (ref "VT7") (pin "6") (pinfunction "D_6") (pintype "passive"))
    )
    (net (code "67") (name "Net-(U4-HO)") (class "Default")
      (node (ref "R25") (pin "1") (pinfunction "1_1") (pintype "passive"))
      (node (ref "U4") (pin "7") (pinfunction "HO_7") (pintype "output"))
    )
    (net (code "68") (name "Net-(U4-LO)") (class "Default")
      (node (ref "R24") (pin "1") (pinfunction "1_1") (pintype "passive"))
      (node (ref "U4") (pin "5") (pinfunction "LO_5") (pintype "output"))
    )
    (net (code "69") (name "Net-(U4-VB)") (class "Default")
      (node (ref "C17") (pin "1") (pinfunction "1_1") (pintype "passive"))
      (node (ref "U4") (pin "8") (pinfunction "VB_8") (pintype "power_in"))
      (node (ref "VD9") (pin "2") (pinfunction "K_2") (pintype "passive"))
    )
    (net (code "70") (name "Net-(U4-VS)") (class "Default")
      (node (ref "C17") (pin "2") (pinfunction "2_2") (pintype "passive"))
      (node (ref "L2") (pin "2") (pinfunction "2_2") (pintype "passive"))
      (node (ref "U4") (pin "6") (pinfunction "VS_6") (pintype "power_in"))
      (node (ref "VT6") (pin "3") (pinfunction "S_3") (pintype "passive"))
      (node (ref "VT7") (pin "7") (pinfunction "D_7") (pintype "passive"))
      (node (ref "VT7") (pin "8") (pinfunction "D_8") (pintype "passive"))
    )
    (net (code "71") (name "Net-(U5-HO)") (class "Default")
      (node (ref "R26") (pin "1") (pinfunction "1_1") (pintype "passive"))
      (node (ref "U5") (pin "7") (pinfunction "HO_7") (pintype "output"))
    )
    (net (code "72") (name "Net-(U5-LO)") (class "Default")
      (node (ref "R28") (pin "1") (pinfunction "1_1") (pintype "passive"))
      (node (ref "U5") (pin "5") (pinfunction "LO_5") (pintype "output"))
    )
    (net (code "73") (name "Net-(U5-VB)") (class "Default")
      (node (ref "C20") (pin "1") (pinfunction "1_1") (pintype "passive"))
      (node (ref "U5") (pin "8") (pinfunction "VB_8") (pintype "power_in"))
      (node (ref "VD10") (pin "2") (pinfunction "K_2") (pintype "passive"))
    )
    (net (code "74") (name "Net-(U6-HO)") (class "Default")
      (node (ref "R27") (pin "1") (pinfunction "1_1") (pintype "passive"))
      (node (ref "U6") (pin "7") (pinfunction "HO_7") (pintype "output"))
    )
    (net (code "75") (name "Net-(U6-LO)") (class "Default")
      (node (ref "R29") (pin "1") (pinfunction "1_1") (pintype "passive"))
      (node (ref "U6") (pin "5") (pinfunction "LO_5") (pintype "output"))
    )
    (net (code "76") (name "Net-(U6-VB)") (class "Default")
      (node (ref "C21") (pin "1") (pinfunction "1_1") (pintype "passive"))
      (node (ref "U6") (pin "8") (pinfunction "VB_8") (pintype "power_in"))
      (node (ref "VD11") (pin "2") (pinfunction "K_2") (pintype "passive"))
    )
    (net (code "77") (name "Net-(U7-HO)") (class "Default")
      (node (ref "R32") (pin "1") (pinfunction "1_1") (pintype "passive"))
      (node (ref "U7") (pin "7") (pinfunction "HO_7") (pintype "output"))
    )
    (net (code "78") (name "Net-(U7-LO)") (class "Default")
      (node (ref "R34") (pin "1") (pinfunction "1_1") (pintype "passive"))
      (node (ref "U7") (pin "5") (pinfunction "LO_5") (pintype "output"))
    )
    (net (code "79") (name "Net-(U7-VB)") (class "Default")
      (node (ref "C22") (pin "1") (pinfunction "1_1") (pintype "passive"))
      (node (ref "U7") (pin "8") (pinfunction "VB_8") (pintype "power_in"))
      (node (ref "VD12") (pin "2") (pinfunction "K_2") (pintype "passive"))
    )
    (net (code "80") (name "Net-(U8-HO)") (class "Default")
      (node (ref "R33") (pin "1") (pinfunction "1_1") (pintype "passive"))
      (node (ref "U8") (pin "7") (pinfunction "HO_7") (pintype "output"))
    )
    (net (code "81") (name "Net-(U8-LO)") (class "Default")
      (node (ref "R35") (pin "1") (pinfunction "1_1") (pintype "passive"))
      (node (ref "U8") (pin "5") (pinfunction "LO_5") (pintype "output"))
    )
    (net (code "82") (name "Net-(U8-VB)") (class "Default")
      (node (ref "C23") (pin "1") (pinfunction "1_1") (pintype "passive"))
      (node (ref "U8") (pin "8") (pinfunction "VB_8") (pintype "power_in"))
      (node (ref "VD13") (pin "2") (pinfunction "K_2") (pintype "passive"))
    )
    (net (code "83") (name "Net-(VD1-A)") (class "Default")
      (node (ref "R10") (pin "1") (pinfunction "1_1") (pintype "passive"))
      (node (ref "R4") (pin "2") (pinfunction "2_2") (pintype "passive"))
      (node (ref "VD1") (pin "2") (pinfunction "A_2") (pintype "passive"))
      (node (ref "VT3") (pin "1") (pinfunction "B_1") (pintype "passive"))
      (node (ref "VT4") (pin "1") (pinfunction "B_1") (pintype "passive"))
    )
    (net (code "84") (name "Net-(VD1-K)") (class "Default")
      (node (ref "R1") (pin "2") (pinfunction "2_2") (pintype "passive"))
      (node (ref "R3") (pin "1") (pinfunction "1_1") (pintype "passive"))
      (node (ref "R4") (pin "1") (pinfunction "1_1") (pintype "passive"))
      (node (ref "R6") (pin "1") (pinfunction "1_1") (pintype "passive"))
      (node (ref "VD1") (pin "1") (pinfunction "K_1") (pintype "passive"))
      (node (ref "VD2") (pin "1") (pinfunction "K_1") (pintype "passive"))
      (node (ref "VT1") (pin "1") (pinfunction "S_1") (pintype "passive"))
      (node (ref "VT1") (pin "2") (pinfunction "S_2") (pintype "passive"))
      (node (ref "VT1") (pin "3") (pinfunction "S_3") (pintype "passive"))
      (node (ref "VT3") (pin "2") (pinfunction "E_2") (pintype "passive"))
      (node (ref "VT4") (pin "2") (pinfunction "E_2") (pintype "passive"))
    )
    (net (code "85") (name "Net-(VD2-A)") (class "Default")
      (node (ref "VD2") (pin "2") (pinfunction "A_2") (pintype "passive"))
      (node (ref "VD4") (pin "1") (pinfunction "K_1") (pintype "passive"))
    )
    (net (code "86") (name "Net-(VD4-A)") (class "Default")
      (node (ref "R13") (pin "2") (pinfunction "2_2") (pintype "passive"))
      (node (ref "VD4") (pin "2") (pinfunction "A_2") (pintype "passive"))
      (node (ref "VT1") (pin "4") (pinfunction "G_4") (pintype "passive"))
      (node (ref "VT2") (pin "4") (pinfunction "G_4") (pintype "passive"))
      (node (ref "VT3") (pin "3") (pinfunction "C_3") (pintype "passive"))
    )
    (net (code "87") (name "Net-(VT1-D-Pad5)") (class "Default")
      (node (ref "VT1") (pin "5") (pinfunction "D_5") (pintype "passive"))
      (node (ref "VT1") (pin "6") (pinfunction "D_6") (pintype "passive"))
      (node (ref "VT1") (pin "7") (pinfunction "D_7") (pintype "passive"))
      (node (ref "VT1") (pin "8") (pinfunction "D_8") (pintype "passive"))
      (node (ref "VT2") (pin "5") (pinfunction "D_5") (pintype "passive"))
      (node (ref "VT2") (pin "6") (pinfunction "D_6") (pintype "passive"))
      (node (ref "VT2") (pin "7") (pinfunction "D_7") (pintype "passive"))
      (node (ref "VT2") (pin "8") (pinfunction "D_8") (pintype "passive"))
    )
    (net (code "88") (name "Net-(VT4-C)") (class "Default")
      (node (ref "R9") (pin "2") (pinfunction "2_2") (pintype "passive"))
      (node (ref "VT4") (pin "3") (pinfunction "C_3") (pintype "passive"))
    )
    (net (code "89") (name "Net-(VT6A-G)") (class "Default")
      (node (ref "R20") (pin "2") (pinfunction "2_2") (pintype "passive"))
      (node (ref "VT6") (pin "2") (pinfunction "G_2") (pintype "passive"))
    )
    (net (code "90") (name "Net-(VT6B-G)") (class "Default")
      (node (ref "R25") (pin "2") (pinfunction "2_2") (pintype "passive"))
      (node (ref "VT6") (pin "4") (pinfunction "G_4") (pintype "passive"))
    )
    (net (code "91") (name "Net-(VT7A-G)") (class "Default")
      (node (ref "R24") (pin "2") (pinfunction "2_2") (pintype "passive"))
      (node (ref "VT7") (pin "2") (pinfunction "G_2") (pintype "passive"))
    )
    (net (code "92") (name "Net-(VT7B-G)") (class "Default")
      (node (ref "R22") (pin "2") (pinfunction "2_2") (pintype "passive"))
      (node (ref "VT7") (pin "4") (pinfunction "G_4") (pintype "passive"))
    )
    (net (code "93") (name "Net-(VT8A-G)") (class "Default")
      (node (ref "R32") (pin "2") (pinfunction "2_2") (pintype "passive"))
      (node (ref "VT8") (pin "2") (pinfunction "G_2") (pintype "passive"))
    )
    (net (code "94") (name "Net-(VT8B-G)") (class "Default")
      (node (ref "R33") (pin "2") (pinfunction "2_2") (pintype "passive"))
      (node (ref "VT8") (pin "4") (pinfunction "G_4") (pintype "passive"))
    )
    (net (code "95") (name "Net-(VT9A-G)") (class "Default")
      (node (ref "R26") (pin "2") (pinfunction "2_2") (pintype "passive"))
      (node (ref "VT9") (pin "2") (pinfunction "G_2") (pintype "passive"))
    )
    (net (code "96") (name "Net-(VT9B-G)") (class "Default")
      (node (ref "R27") (pin "2") (pinfunction "2_2") (pintype "passive"))
      (node (ref "VT9") (pin "4") (pinfunction "G_4") (pintype "passive"))
    )
    (net (code "97") (name "Net-(VT10A-G)") (class "Default")
      (node (ref "R28") (pin "2") (pinfunction "2_2") (pintype "passive"))
      (node (ref "VT10") (pin "2") (pinfunction "G_2") (pintype "passive"))
    )
    (net (code "98") (name "Net-(VT10B-G)") (class "Default")
      (node (ref "R34") (pin "2") (pinfunction "2_2") (pintype "passive"))
      (node (ref "VT10") (pin "4") (pinfunction "G_4") (pintype "passive"))
    )
    (net (code "99") (name "Net-(VT11A-G)") (class "Default")
      (node (ref "R29") (pin "2") (pinfunction "2_2") (pintype "passive"))
      (node (ref "VT11") (pin "2") (pinfunction "G_2") (pintype "passive"))
    )
    (net (code "100") (name "Net-(VT11B-G)") (class "Default")
      (node (ref "R35") (pin "2") (pinfunction "2_2") (pintype "passive"))
      (node (ref "VT11") (pin "4") (pinfunction "G_4") (pintype "passive"))
    )
    (net (code "101") (name "Vmainbus") (class "Default")
      (node (ref "C11") (pin "1") (pinfunction "1_1") (pintype "passive"))
      (node (ref "C12") (pin "2") (pinfunction "2_2") (pintype "passive"))
      (node (ref "R2") (pin "1") (pinfunction "1_1") (pintype "passive"))
      (node (ref "U1") (pin "1") (pinfunction "VIN_1") (pintype "power_in"))
      (node (ref "VT2") (pin "1") (pinfunction "S_1") (pintype "passive"))
      (node (ref "VT2") (pin "2") (pinfunction "S_2") (pintype "passive"))
      (node (ref "VT2") (pin "3") (pinfunction "S_3") (pintype "passive"))
      (node (ref "VT6") (pin "7") (pinfunction "D_7") (pintype "passive"))
      (node (ref "VT6") (pin "8") (pinfunction "D_8") (pintype "passive"))
    )
    (net (code "102") (name "Vsecondarybus") (class "Default")
      (node (ref "C14") (pin "2") (pinfunction "2_2") (pintype "passive"))
      (node (ref "C16") (pin "1") (pinfunction "1_1") (pintype "passive"))
      (node (ref "C18") (pin "1") (pinfunction "1_1") (pintype "passive"))
      (node (ref "C19") (pin "1") (pinfunction "1_1") (pintype "passive"))
      (node (ref "R21") (pin "2") (pinfunction "2_2") (pintype "passive"))
      (node (ref "VT6") (pin "5") (pinfunction "D_5") (pintype "passive"))
      (node (ref "VT6") (pin "6") (pinfunction "D_6") (pintype "passive"))
      (node (ref "VT8") (pin "5") (pinfunction "D_5") (pintype "passive"))
      (node (ref "VT8") (pin "6") (pinfunction "D_6") (pintype "passive"))
      (node (ref "VT8") (pin "7") (pinfunction "D_7") (pintype "passive"))
      (node (ref "VT8") (pin "8") (pinfunction "D_8") (pintype "passive"))
      (node (ref "VT9") (pin "5") (pinfunction "D_5") (pintype "passive"))
      (node (ref "VT9") (pin "6") (pinfunction "D_6") (pintype "passive"))
      (node (ref "VT9") (pin "7") (pinfunction "D_7") (pintype "passive"))
      (node (ref "VT9") (pin "8") (pinfunction "D_8") (pintype "passive"))
    )
    (net (code "103") (name "unconnected-(U1-PGD-Pad3)") (class "Default")
      (node (ref "U1") (pin "3") (pinfunction "PGD_3") (pintype "output"))
    )
  )
)
